# scanner.net
KiCad netlist of a schematic drawn in EAGLE
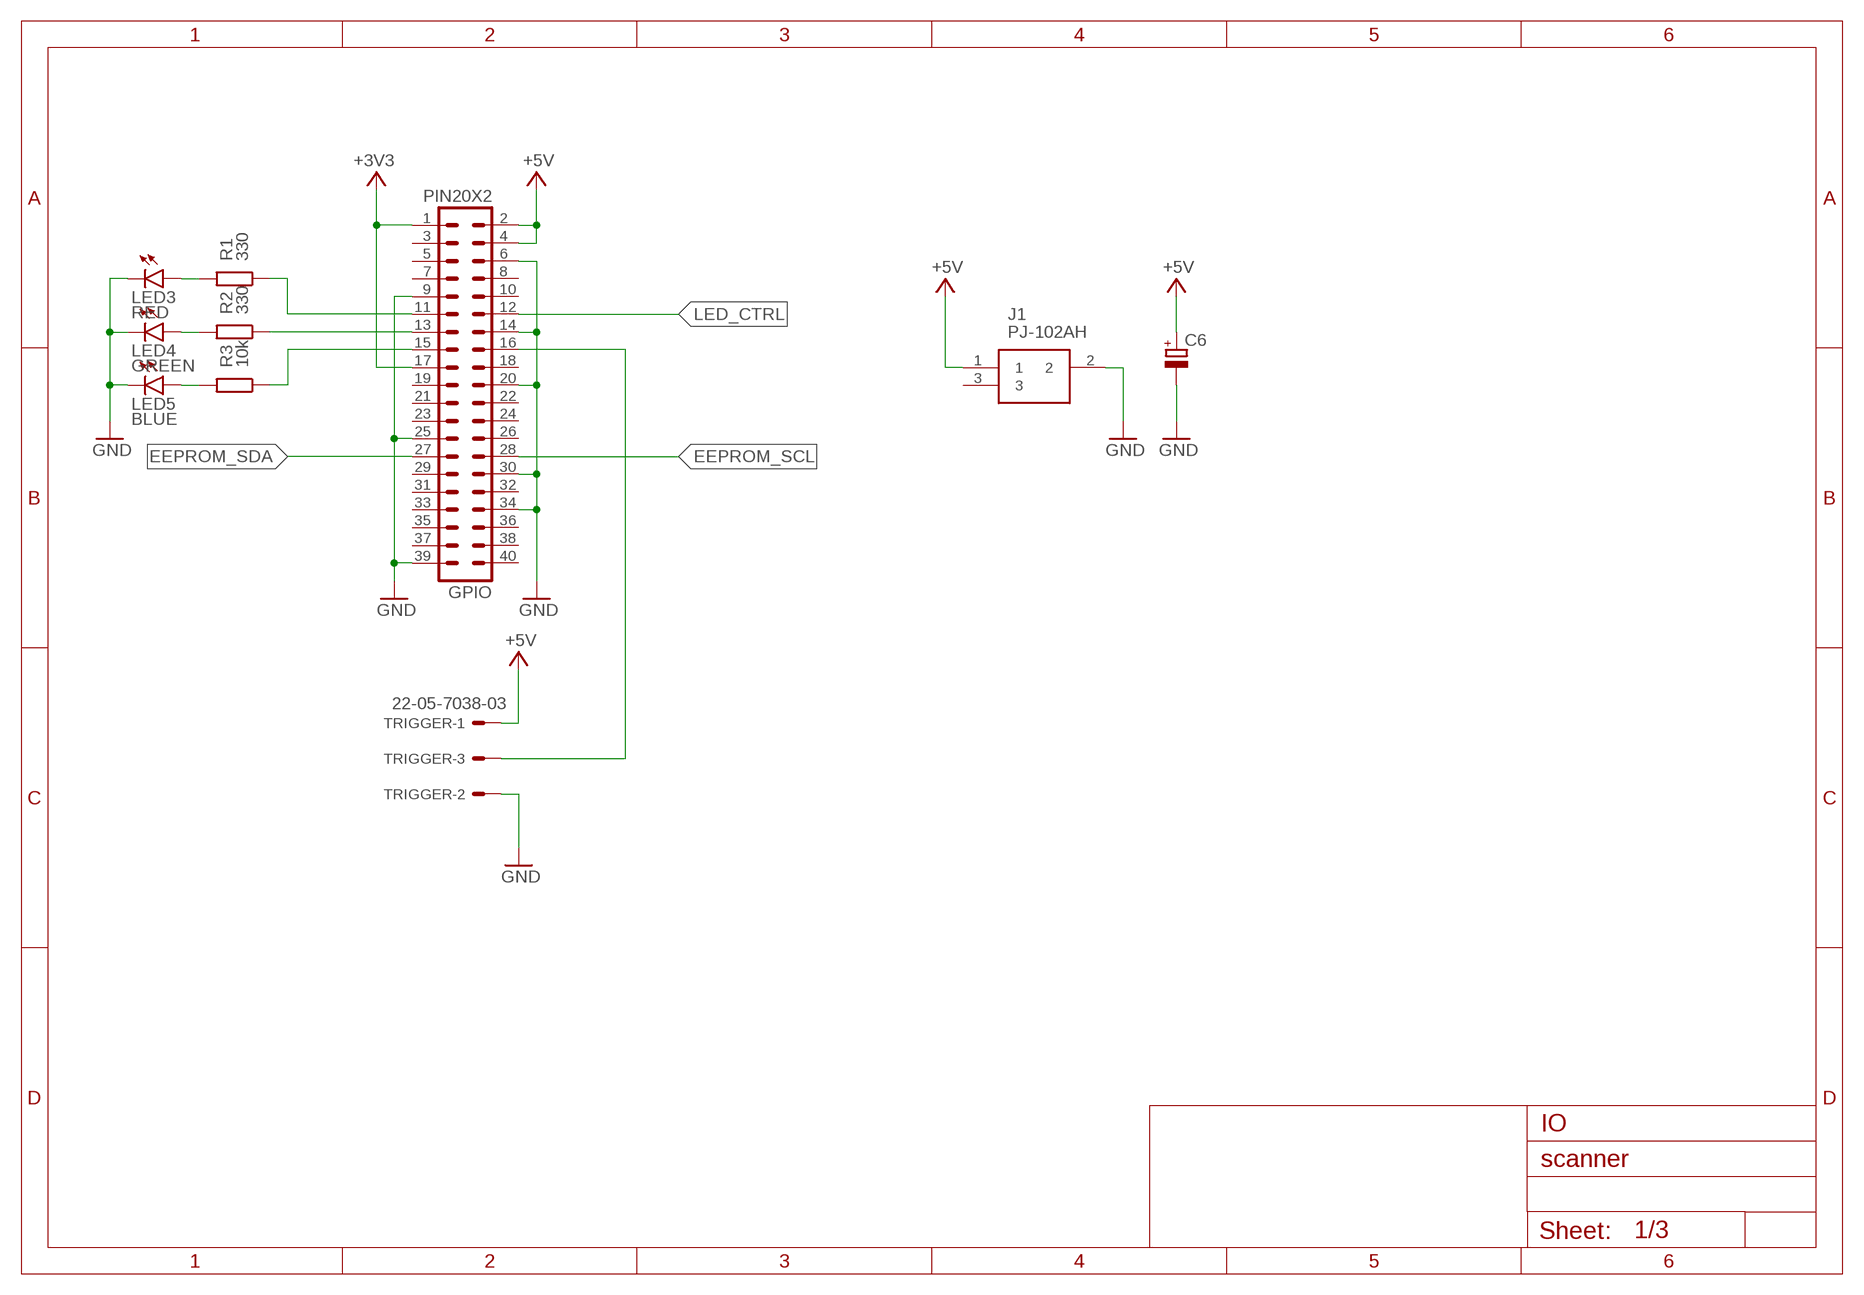
[diagram p0: schematic, sheet 1]
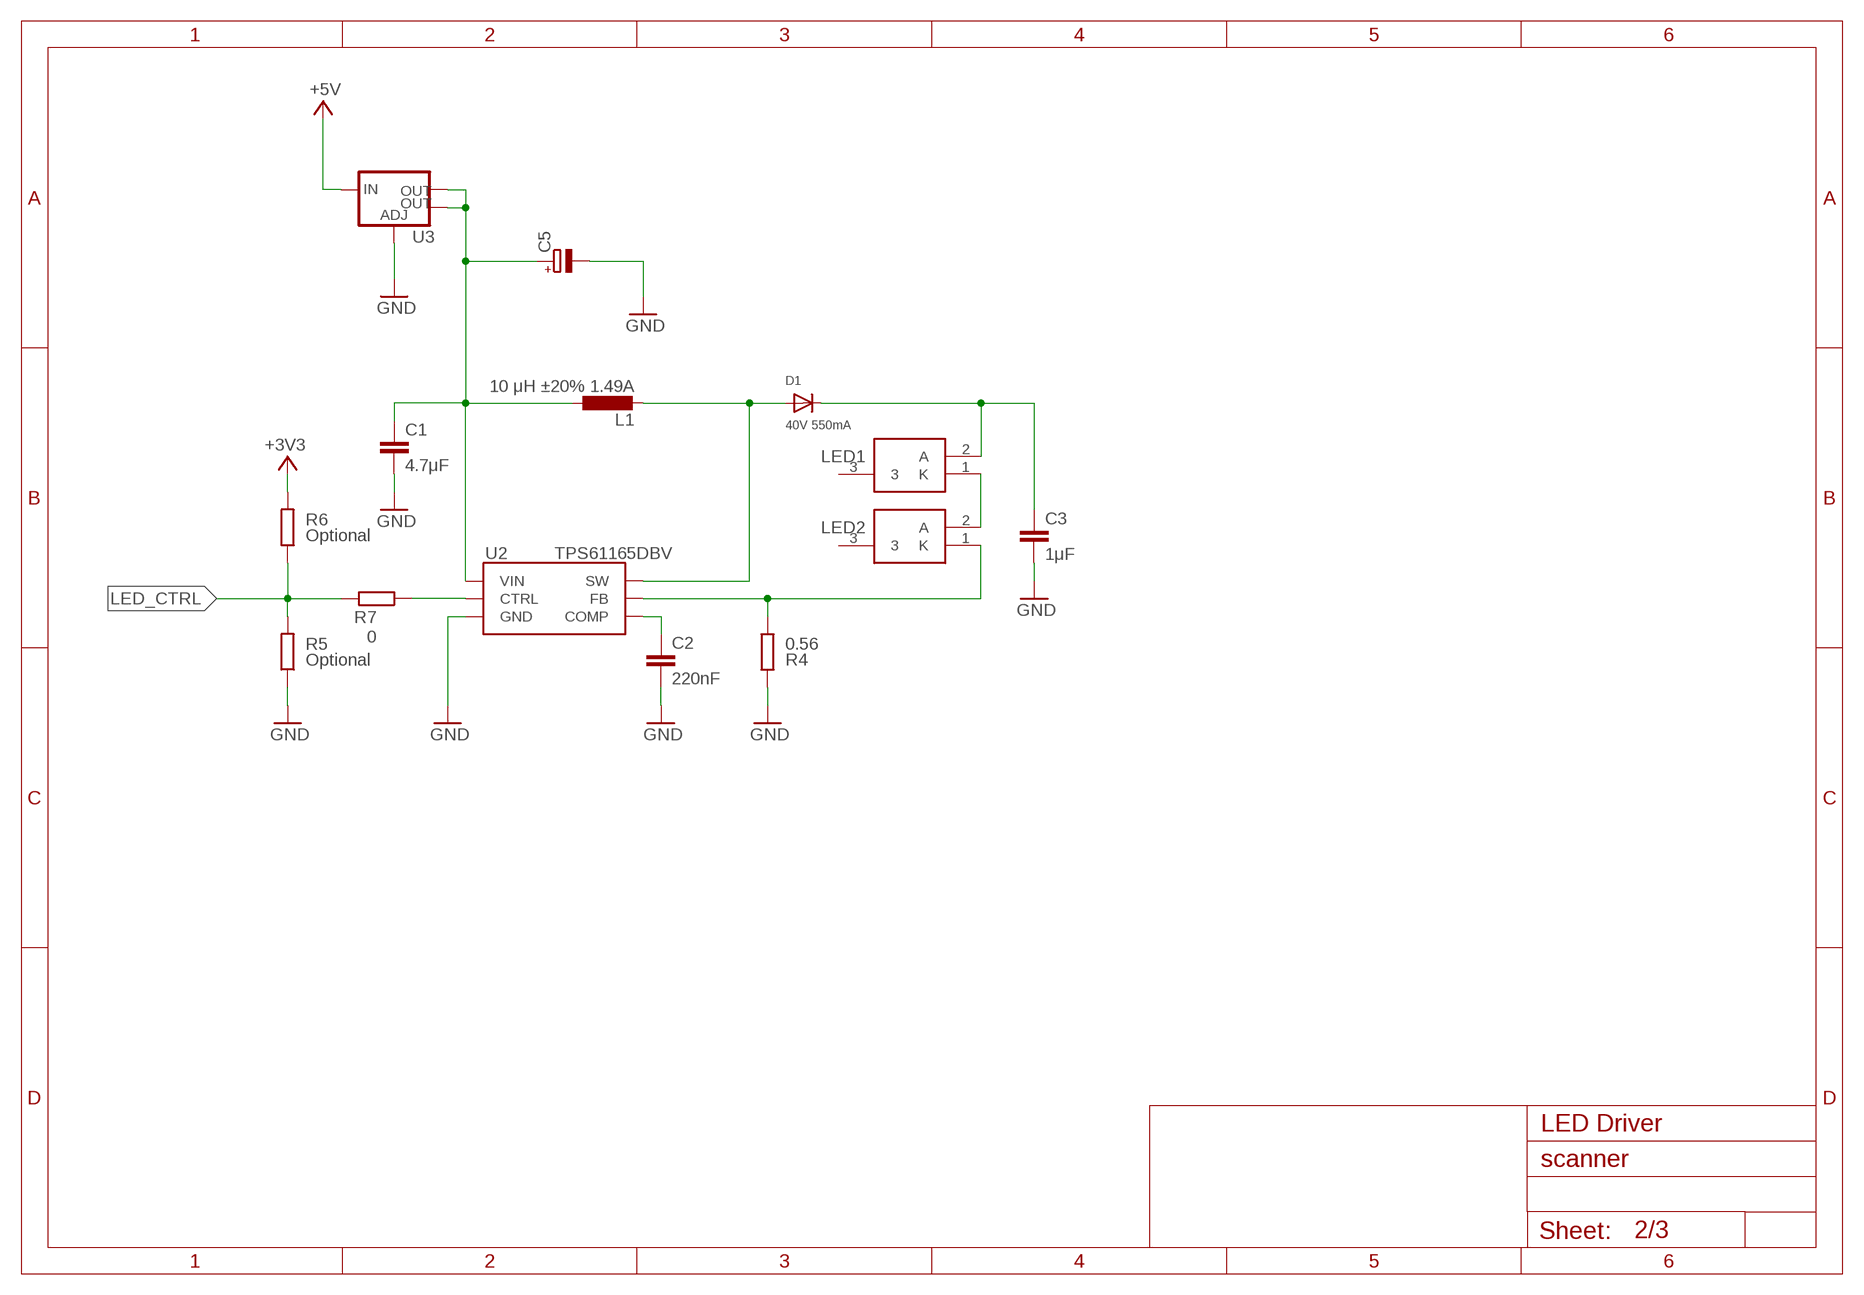
[diagram p1: schematic, sheet 2]
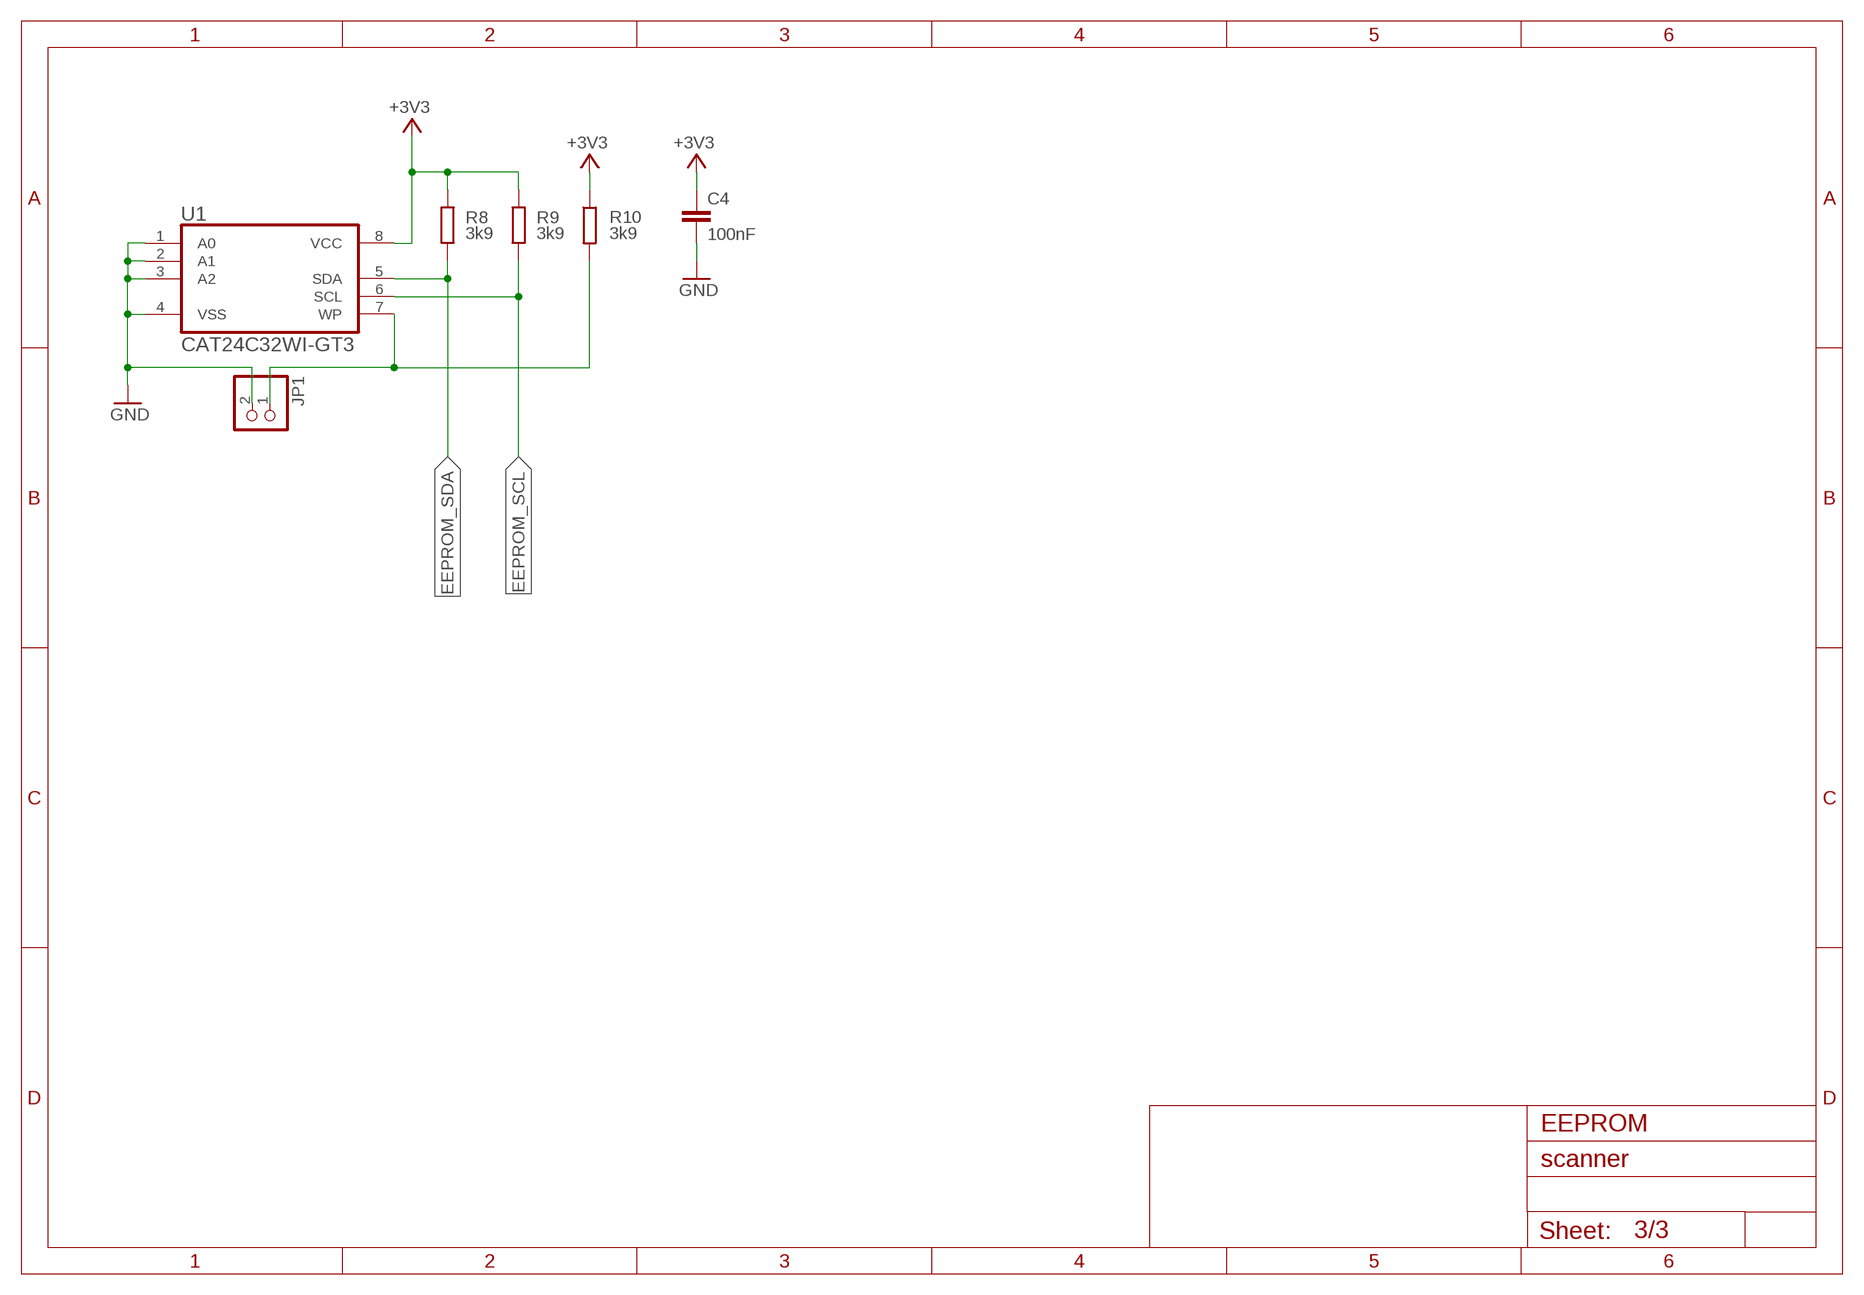
[diagram p2: schematic, sheet 3]

(export (version "E")
  (design (tool "Eeschema 10.0.6"))
  (components
    (comp (ref "C1")
      (value "4.7μF")
      (footprint "eagle-import:C0805K")
      (libsource (lib "eagle-import") (part "C-EUC0805K"))
    )
    (comp (ref "C2")
      (value "220nF")
      (footprint "eagle-import:C0805K")
      (libsource (lib "eagle-import") (part "C-EUC0805K"))
    )
    (comp (ref "C3")
      (value "1μF")
      (footprint "eagle-import:C0805K")
      (libsource (lib "eagle-import") (part "C-EUC0805K"))
    )
    (comp (ref "C5")
      (value "CPOL-EUCT6032")
      (footprint "eagle-import:CT6032")
      (libsource (lib "eagle-import") (part "CPOL-EUCT6032"))
    )
    (comp (ref "D1")
      (value "40V 550mA")
      (footprint "eagle-import:SOD-123")
      (libsource (lib "eagle-import") (part "DIODESOD-123"))
    )
    (comp (ref "L1")
      (value "10 μH ±20% 1.49A")
      (footprint "eagle-import:D53LC")
      (libsource (lib "eagle-import") (part "D53LC"))
    )
    (comp (ref "LED1")
      (value "LW_W5SM-JYKY-JKQL-1")
      (footprint "eagle-import:LWW5SMJYKYJKQL1")
      (fields
        (field (name "MANUFACTURER_PART_NUMBER") "LW W5SM-JYKY-JKQL-1")
        (field (name "MOUSER_PART_NUMBER") "720-LWW5SMJYKYJKQL1")
      )
      (libsource (lib "eagle-import") (part "LW_W5SM-JYKY-JKQL-1"))
    )
    (comp (ref "LED2")
      (value "LW_W5SM-JYKY-JKQL-1")
      (footprint "eagle-import:LWW5SMJYKYJKQL1")
      (fields
        (field (name "MANUFACTURER_PART_NUMBER") "LW W5SM-JYKY-JKQL-1")
        (field (name "MOUSER_PART_NUMBER") "720-LWW5SMJYKYJKQL1")
      )
      (libsource (lib "eagle-import") (part "LW_W5SM-JYKY-JKQL-1"))
    )
    (comp (ref "R4")
      (value "0.56")
      (footprint "eagle-import:M0805")
      (fields (field (name "TOLERANCE") "5%"))
      (libsource (lib "eagle-import") (part "R-EU_M0805"))
    )
    (comp (ref "R5")
      (value "Optional")
      (footprint "eagle-import:M0805")
      (fields (field (name "TOLERANCE") "5%"))
      (libsource (lib "eagle-import") (part "R-EU_M0805"))
    )
    (comp (ref "R6")
      (value "Optional")
      (footprint "eagle-import:M0805")
      (fields (field (name "TOLERANCE") "5%"))
      (libsource (lib "eagle-import") (part "R-EU_M0805"))
    )
    (comp (ref "R7")
      (value "0")
      (footprint "eagle-import:M0805")
      (fields (field (name "TOLERANCE") "5%"))
      (libsource (lib "eagle-import") (part "R-EU_M0805"))
    )
    (comp (ref "U2")
      (value "TPS61165DBV")
      (footprint "eagle-import:SOT-23-6")
      (libsource (lib "eagle-import") (part "TPS61165DBV"))
    )
    (comp (ref "U3")
      (value "V_REG_LM1117SOT223")
      (footprint "eagle-import:SOT223")
      (libsource (lib "eagle-import") (part "V_REG_LM1117SOT223"))
    )
    (comp (ref "C4")
      (value "100nF")
      (footprint "eagle-import:C0805K")
      (libsource (lib "eagle-import") (part "C-EUC0805K"))
    )
    (comp (ref "JP1")
      (value "PINHD-1X2")
      (footprint "eagle-import:1X02")
      (libsource (lib "eagle-import") (part "PINHD-1X2"))
    )
    (comp (ref "R8")
      (value "3k9")
      (footprint "eagle-import:M0805")
      (fields (field (name "TOLERANCE") "5%"))
      (libsource (lib "eagle-import") (part "R-EU_M0805"))
    )
    (comp (ref "R9")
      (value "3k9")
      (footprint "eagle-import:M0805")
      (fields (field (name "TOLERANCE") "5%"))
      (libsource (lib "eagle-import") (part "R-EU_M0805"))
    )
    (comp (ref "R10")
      (value "3k9")
      (footprint "eagle-import:M0805")
      (fields (field (name "TOLERANCE") "5%"))
      (libsource (lib "eagle-import") (part "R-EU_M0805"))
    )
    (comp (ref "U1")
      (value "CAT24C32WI-GT3")
      (footprint "eagle-import:SOIC127P600X175-8N")
      (libsource (lib "eagle-import") (part "CAT24C32WI-GT3"))
    )
    (comp (ref "C6")
      (value "CPOL-EUCT6032")
      (footprint "eagle-import:CT6032")
      (libsource (lib "eagle-import") (part "CPOL-EUCT6032"))
    )
    (comp (ref "GPIO")
      (value "PIN20X2")
      (footprint "eagle-import:PIN_20X2")
      (libsource (lib "eagle-import") (part "PIN20X2"))
    )
    (comp (ref "J1")
      (value "PJ-102AH")
      (footprint "eagle-import:PJ-102AH")
      (fields (field (name "MOUSER_PART_NUMBER") "490-PJ-102AH"))
      (libsource (lib "eagle-import") (part "PJ-102AH"))
    )
    (comp (ref "LED3")
      (value "RED")
      (footprint "eagle-import:CHIP-LED0805")
      (libsource (lib "eagle-import") (part "LEDCHIP-LED0805"))
    )
    (comp (ref "LED4")
      (value "GREEN")
      (footprint "eagle-import:CHIP-LED0805")
      (libsource (lib "eagle-import") (part "LEDCHIP-LED0805"))
    )
    (comp (ref "LED5")
      (value "BLUE")
      (footprint "eagle-import:CHIP-LED0805")
      (libsource (lib "eagle-import") (part "LEDCHIP-LED0805"))
    )
    (comp (ref "R1")
      (value "330")
      (footprint "eagle-import:M0805")
      (fields (field (name "TOLERANCE") "5%"))
      (libsource (lib "eagle-import") (part "R-EU_M0805"))
    )
    (comp (ref "R2")
      (value "330")
      (footprint "eagle-import:M0805")
      (fields (field (name "TOLERANCE") "5%"))
      (libsource (lib "eagle-import") (part "R-EU_M0805"))
    )
    (comp (ref "R3")
      (value "10k")
      (footprint "eagle-import:M0805")
      (fields (field (name "TOLERANCE") "5%"))
      (libsource (lib "eagle-import") (part "R-EU_M0805"))
    )
    (comp (ref "TRIGGER")
      (value "22-05-7038-03")
      (footprint "eagle-import:7395-03")
      (fields (field (name "MF") "MOLEX"))
      (libsource (lib "eagle-import") (part "22-?-0305-7038"))
    )
  )
  (nets
    (net (code "1") (name "+3V3") (class "Default")
      (node (ref "C4") (pin "1") (pinfunction "1_1") (pintype "passive"))
      (node (ref "GPIO") (pin "1") (pinfunction "1_1") (pintype "passive"))
      (node (ref "GPIO") (pin "17") (pinfunction "17_17") (pintype "passive"))
      (node (ref "R10") (pin "1") (pinfunction "1_1") (pintype "passive"))
      (node (ref "R6") (pin "2") (pinfunction "2_2") (pintype "passive"))
      (node (ref "R8") (pin "2") (pinfunction "2_2") (pintype "passive"))
      (node (ref "R9") (pin "2") (pinfunction "2_2") (pintype "passive"))
      (node (ref "U1") (pin "8") (pinfunction "VCC_8") (pintype "passive"))
    )
    (net (code "2") (name "+5V") (class "Default")
      (node (ref "C6") (pin "+") (pinfunction "+_+") (pintype "passive"))
      (node (ref "GPIO") (pin "2") (pinfunction "2_2") (pintype "passive"))
      (node (ref "GPIO") (pin "4") (pinfunction "4_4") (pintype "passive"))
      (node (ref "J1") (pin "1") (pinfunction "1_1") (pintype "bidirectional"))
      (node (ref "TRIGGER") (pin "1") (pinfunction "S_1") (pintype "passive"))
      (node (ref "U3") (pin "3") (pinfunction "IN_3") (pintype "input"))
    )
    (net (code "3") (name "EEPROM_SCL") (class "Default")
      (node (ref "GPIO") (pin "28") (pinfunction "28_28") (pintype "passive"))
      (node (ref "R9") (pin "1") (pinfunction "1_1") (pintype "passive"))
      (node (ref "U1") (pin "6") (pinfunction "SCL_6") (pintype "input"))
    )
    (net (code "4") (name "EEPROM_SDA") (class "Default")
      (node (ref "GPIO") (pin "27") (pinfunction "27_27") (pintype "passive"))
      (node (ref "R8") (pin "1") (pinfunction "1_1") (pintype "passive"))
      (node (ref "U1") (pin "5") (pinfunction "SDA_5") (pintype "bidirectional"))
    )
    (net (code "5") (name "GND") (class "Default")
      (node (ref "C1") (pin "2") (pinfunction "2_2") (pintype "passive"))
      (node (ref "C2") (pin "2") (pinfunction "2_2") (pintype "passive"))
      (node (ref "C3") (pin "2") (pinfunction "2_2") (pintype "passive"))
      (node (ref "C4") (pin "2") (pinfunction "2_2") (pintype "passive"))
      (node (ref "C5") (pin "-") (pinfunction "-_-") (pintype "passive"))
      (node (ref "C6") (pin "-") (pinfunction "-_-") (pintype "passive"))
      (node (ref "GPIO") (pin "14") (pinfunction "14_14") (pintype "passive"))
      (node (ref "GPIO") (pin "20") (pinfunction "20_20") (pintype "passive"))
      (node (ref "GPIO") (pin "25") (pinfunction "25_25") (pintype "passive"))
      (node (ref "GPIO") (pin "30") (pinfunction "30_30") (pintype "passive"))
      (node (ref "GPIO") (pin "34") (pinfunction "34_34") (pintype "passive"))
      (node (ref "GPIO") (pin "39") (pinfunction "39_39") (pintype "passive"))
      (node (ref "GPIO") (pin "6") (pinfunction "6_6") (pintype "passive"))
      (node (ref "GPIO") (pin "9") (pinfunction "9_9") (pintype "passive"))
      (node (ref "J1") (pin "2") (pinfunction "2_2") (pintype "bidirectional"))
      (node (ref "JP1") (pin "2") (pinfunction "2_2") (pintype "passive"))
      (node (ref "LED3") (pin "C") (pinfunction "C_C") (pintype "passive"))
      (node (ref "LED4") (pin "C") (pinfunction "C_C") (pintype "passive"))
      (node (ref "LED5") (pin "C") (pinfunction "C_C") (pintype "passive"))
      (node (ref "R4") (pin "2") (pinfunction "2_2") (pintype "passive"))
      (node (ref "R5") (pin "1") (pinfunction "1_1") (pintype "passive"))
      (node (ref "TRIGGER") (pin "2") (pinfunction "S_2") (pintype "passive"))
      (node (ref "U1") (pin "1") (pinfunction "A0_1") (pintype "input"))
      (node (ref "U1") (pin "2") (pinfunction "A1_2") (pintype "input"))
      (node (ref "U1") (pin "3") (pinfunction "A2_3") (pintype "input"))
      (node (ref "U1") (pin "4") (pinfunction "VSS_4") (pintype "passive"))
      (node (ref "U2") (pin "4") (pinfunction "GND_4") (pintype "power_in"))
      (node (ref "U3") (pin "1") (pinfunction "ADJ_1") (pintype "input"))
    )
    (net (code "6") (name "LED_CTRL") (class "Default")
      (node (ref "GPIO") (pin "12") (pinfunction "12_12") (pintype "passive"))
      (node (ref "R5") (pin "2") (pinfunction "2_2") (pintype "passive"))
      (node (ref "R6") (pin "1") (pinfunction "1_1") (pintype "passive"))
      (node (ref "R7") (pin "2") (pinfunction "2_2") (pintype "passive"))
    )
    (net (code "7") (name "Net-(GPIO-Pad11)") (class "Default")
      (node (ref "GPIO") (pin "11") (pinfunction "11_11") (pintype "passive"))
      (node (ref "R1") (pin "1") (pinfunction "1_1") (pintype "passive"))
    )
    (net (code "8") (name "Net-(GPIO-Pad13)") (class "Default")
      (node (ref "GPIO") (pin "13") (pinfunction "13_13") (pintype "passive"))
      (node (ref "R2") (pin "1") (pinfunction "1_1") (pintype "passive"))
    )
    (net (code "9") (name "Net-(GPIO-Pad15)") (class "Default")
      (node (ref "GPIO") (pin "15") (pinfunction "15_15") (pintype "passive"))
      (node (ref "R3") (pin "1") (pinfunction "1_1") (pintype "passive"))
    )
    (net (code "10") (name "Net-(LED1-A)") (class "Default")
      (node (ref "C3") (pin "1") (pinfunction "1_1") (pintype "passive"))
      (node (ref "D1") (pin "C") (pinfunction "C_C") (pintype "passive"))
      (node (ref "LED1") (pin "2") (pinfunction "A_2") (pintype "bidirectional"))
    )
    (net (code "11") (name "Net-(LED1-K)") (class "Default")
      (node (ref "LED1") (pin "1") (pinfunction "K_1") (pintype "bidirectional"))
      (node (ref "LED2") (pin "2") (pinfunction "A_2") (pintype "bidirectional"))
    )
    (net (code "12") (name "Net-(LED2-K)") (class "Default")
      (node (ref "LED2") (pin "1") (pinfunction "K_1") (pintype "bidirectional"))
      (node (ref "R4") (pin "1") (pinfunction "1_1") (pintype "passive"))
      (node (ref "U2") (pin "6") (pinfunction "FB_6") (pintype "input"))
    )
    (net (code "13") (name "Net-(LED3-PadA)") (class "Default")
      (node (ref "LED3") (pin "A") (pinfunction "A_A") (pintype "passive"))
      (node (ref "R1") (pin "2") (pinfunction "2_2") (pintype "passive"))
    )
    (net (code "14") (name "Net-(LED4-PadA)") (class "Default")
      (node (ref "LED4") (pin "A") (pinfunction "A_A") (pintype "passive"))
      (node (ref "R2") (pin "2") (pinfunction "2_2") (pintype "passive"))
    )
    (net (code "15") (name "Net-(LED5-PadA)") (class "Default")
      (node (ref "LED5") (pin "A") (pinfunction "A_A") (pintype "passive"))
      (node (ref "R3") (pin "2") (pinfunction "2_2") (pintype "passive"))
    )
    (net (code "16") (name "Net-(TRIGGERC-S)") (class "Default")
      (node (ref "GPIO") (pin "16") (pinfunction "16_16") (pintype "passive"))
      (node (ref "TRIGGER") (pin "3") (pinfunction "S_3") (pintype "passive"))
    )
    (net (code "17") (name "Net-(U1-WP)") (class "Default")
      (node (ref "JP1") (pin "1") (pinfunction "1_1") (pintype "passive"))
      (node (ref "R10") (pin "2") (pinfunction "2_2") (pintype "passive"))
      (node (ref "U1") (pin "7") (pinfunction "WP_7") (pintype "input"))
    )
    (net (code "18") (name "Net-(U2-COMP)") (class "Default")
      (node (ref "C2") (pin "1") (pinfunction "1_1") (pintype "passive"))
      (node (ref "U2") (pin "5") (pinfunction "COMP_5") (pintype "output"))
    )
    (net (code "19") (name "Net-(U2-CTRL)") (class "Default")
      (node (ref "R7") (pin "1") (pinfunction "1_1") (pintype "passive"))
      (node (ref "U2") (pin "2") (pinfunction "CTRL_2") (pintype "input"))
    )
    (net (code "20") (name "Net-(U2-SW)") (class "Default")
      (node (ref "D1") (pin "A") (pinfunction "A_A") (pintype "passive"))
      (node (ref "L1") (pin "2") (pinfunction "2_2") (pintype "passive"))
      (node (ref "U2") (pin "3") (pinfunction "SW_3") (pintype "output"))
    )
    (net (code "21") (name "Net-(U2-VIN)") (class "Default")
      (node (ref "C1") (pin "1") (pinfunction "1_1") (pintype "passive"))
      (node (ref "C5") (pin "+") (pinfunction "+_+") (pintype "passive"))
      (node (ref "L1") (pin "1") (pinfunction "1_1") (pintype "passive"))
      (node (ref "U2") (pin "1") (pinfunction "VIN_1") (pintype "power_in"))
      (node (ref "U3") (pin "2") (pinfunction "OUT_2") (pintype "output"))
      (node (ref "U3") (pin "4") (pinfunction "OUT_4") (pintype "output"))
    )
    (net (code "22") (name "unconnected-(GPIO-Pad3)") (class "Default")
      (node (ref "GPIO") (pin "3") (pinfunction "3_3") (pintype "passive"))
    )
    (net (code "23") (name "unconnected-(GPIO-Pad5)") (class "Default")
      (node (ref "GPIO") (pin "5") (pinfunction "5_5") (pintype "passive"))
    )
    (net (code "24") (name "unconnected-(GPIO-Pad7)") (class "Default")
      (node (ref "GPIO") (pin "7") (pinfunction "7_7") (pintype "passive"))
    )
    (net (code "25") (name "unconnected-(GPIO-Pad8)") (class "Default")
      (node (ref "GPIO") (pin "8") (pinfunction "8_8") (pintype "passive"))
    )
    (net (code "26") (name "unconnected-(GPIO-Pad10)") (class "Default")
      (node (ref "GPIO") (pin "10") (pinfunction "10_10") (pintype "passive"))
    )
    (net (code "27") (name "unconnected-(GPIO-Pad18)") (class "Default")
      (node (ref "GPIO") (pin "18") (pinfunction "18_18") (pintype "passive"))
    )
    (net (code "28") (name "unconnected-(GPIO-Pad19)") (class "Default")
      (node (ref "GPIO") (pin "19") (pinfunction "19_19") (pintype "passive"))
    )
    (net (code "29") (name "unconnected-(GPIO-Pad21)") (class "Default")
      (node (ref "GPIO") (pin "21") (pinfunction "21_21") (pintype "passive"))
    )
    (net (code "30") (name "unconnected-(GPIO-Pad22)") (class "Default")
      (node (ref "GPIO") (pin "22") (pinfunction "22_22") (pintype "passive"))
    )
    (net (code "31") (name "unconnected-(GPIO-Pad23)") (class "Default")
      (node (ref "GPIO") (pin "23") (pinfunction "23_23") (pintype "passive"))
    )
    (net (code "32") (name "unconnected-(GPIO-Pad24)") (class "Default")
      (node (ref "GPIO") (pin "24") (pinfunction "24_24") (pintype "passive"))
    )
    (net (code "33") (name "unconnected-(GPIO-Pad26)") (class "Default")
      (node (ref "GPIO") (pin "26") (pinfunction "26_26") (pintype "passive"))
    )
    (net (code "34") (name "unconnected-(GPIO-Pad29)") (class "Default")
      (node (ref "GPIO") (pin "29") (pinfunction "29_29") (pintype "passive"))
    )
    (net (code "35") (name "unconnected-(GPIO-Pad31)") (class "Default")
      (node (ref "GPIO") (pin "31") (pinfunction "31_31") (pintype "passive"))
    )
    (net (code "36") (name "unconnected-(GPIO-Pad32)") (class "Default")
      (node (ref "GPIO") (pin "32") (pinfunction "32_32") (pintype "passive"))
    )
    (net (code "37") (name "unconnected-(GPIO-Pad33)") (class "Default")
      (node (ref "GPIO") (pin "33") (pinfunction "33_33") (pintype "passive"))
    )
    (net (code "38") (name "unconnected-(GPIO-Pad35)") (class "Default")
      (node (ref "GPIO") (pin "35") (pinfunction "35_35") (pintype "passive"))
    )
    (net (code "39") (name "unconnected-(GPIO-Pad36)") (class "Default")
      (node (ref "GPIO") (pin "36") (pinfunction "36_36") (pintype "passive"))
    )
    (net (code "40") (name "unconnected-(GPIO-Pad37)") (class "Default")
      (node (ref "GPIO") (pin "37") (pinfunction "37_37") (pintype "passive"))
    )
    (net (code "41") (name "unconnected-(GPIO-Pad38)") (class "Default")
      (node (ref "GPIO") (pin "38") (pinfunction "38_38") (pintype "passive"))
    )
    (net (code "42") (name "unconnected-(GPIO-Pad40)") (class "Default")
      (node (ref "GPIO") (pin "40") (pinfunction "40_40") (pintype "passive"))
    )
    (net (code "43") (name "unconnected-(J1-Pad3)") (class "Default")
      (node (ref "J1") (pin "3") (pinfunction "3_3") (pintype "bidirectional"))
    )
    (net (code "44") (name "unconnected-(LED1-Pad3)") (class "Default")
      (node (ref "LED1") (pin "3") (pinfunction "3_3") (pintype "bidirectional"))
    )
    (net (code "45") (name "unconnected-(LED2-Pad3)") (class "Default")
      (node (ref "LED2") (pin "3") (pinfunction "3_3") (pintype "bidirectional"))
    )
  )
)
